# Application.net
KiCad netlist of a schematic drawn in EAGLE
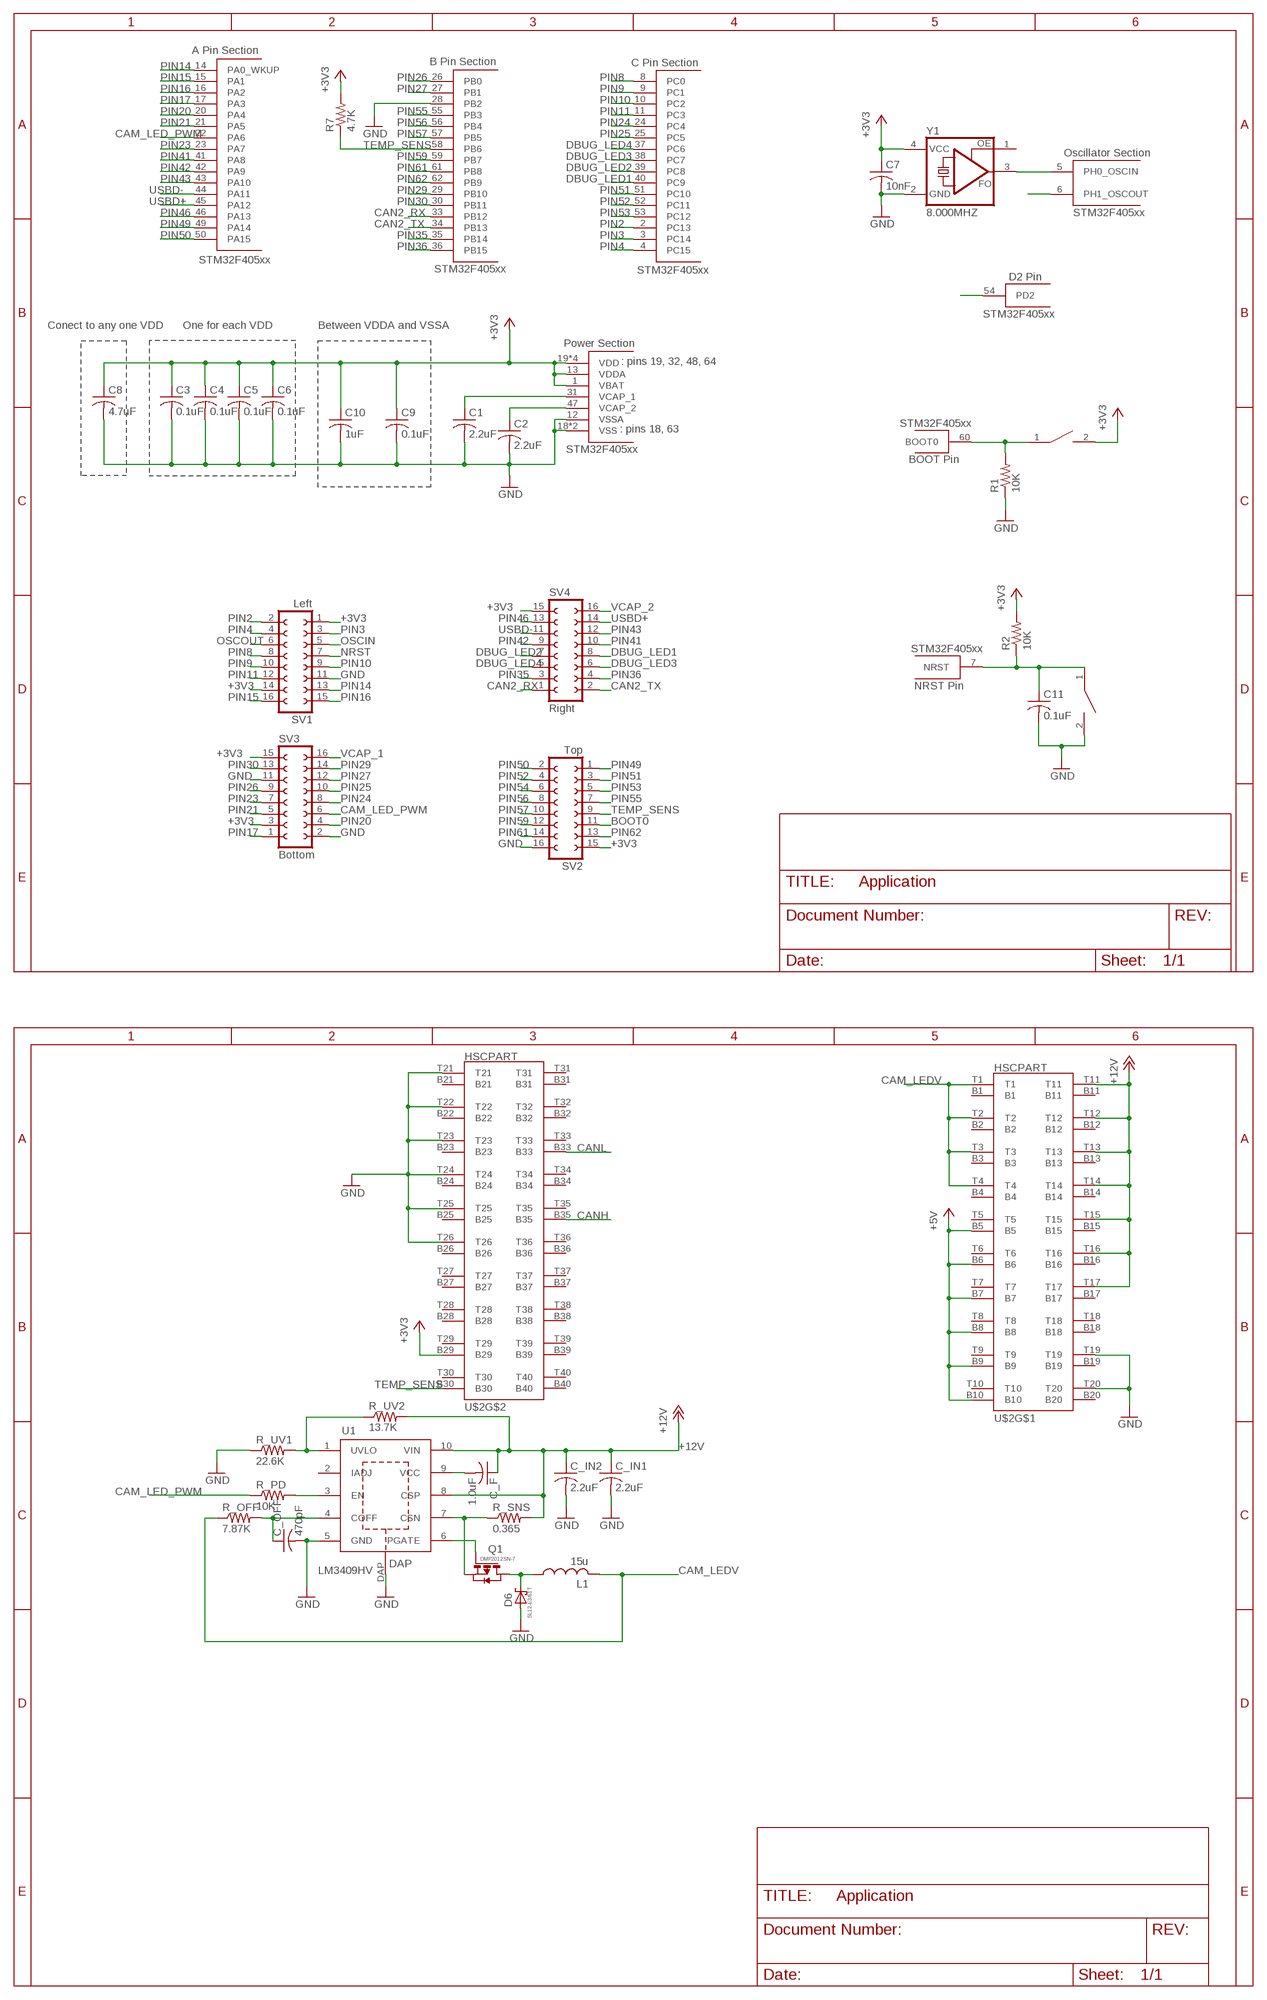
[diagram p0: schematic, sheet 1, part 1 of 2]
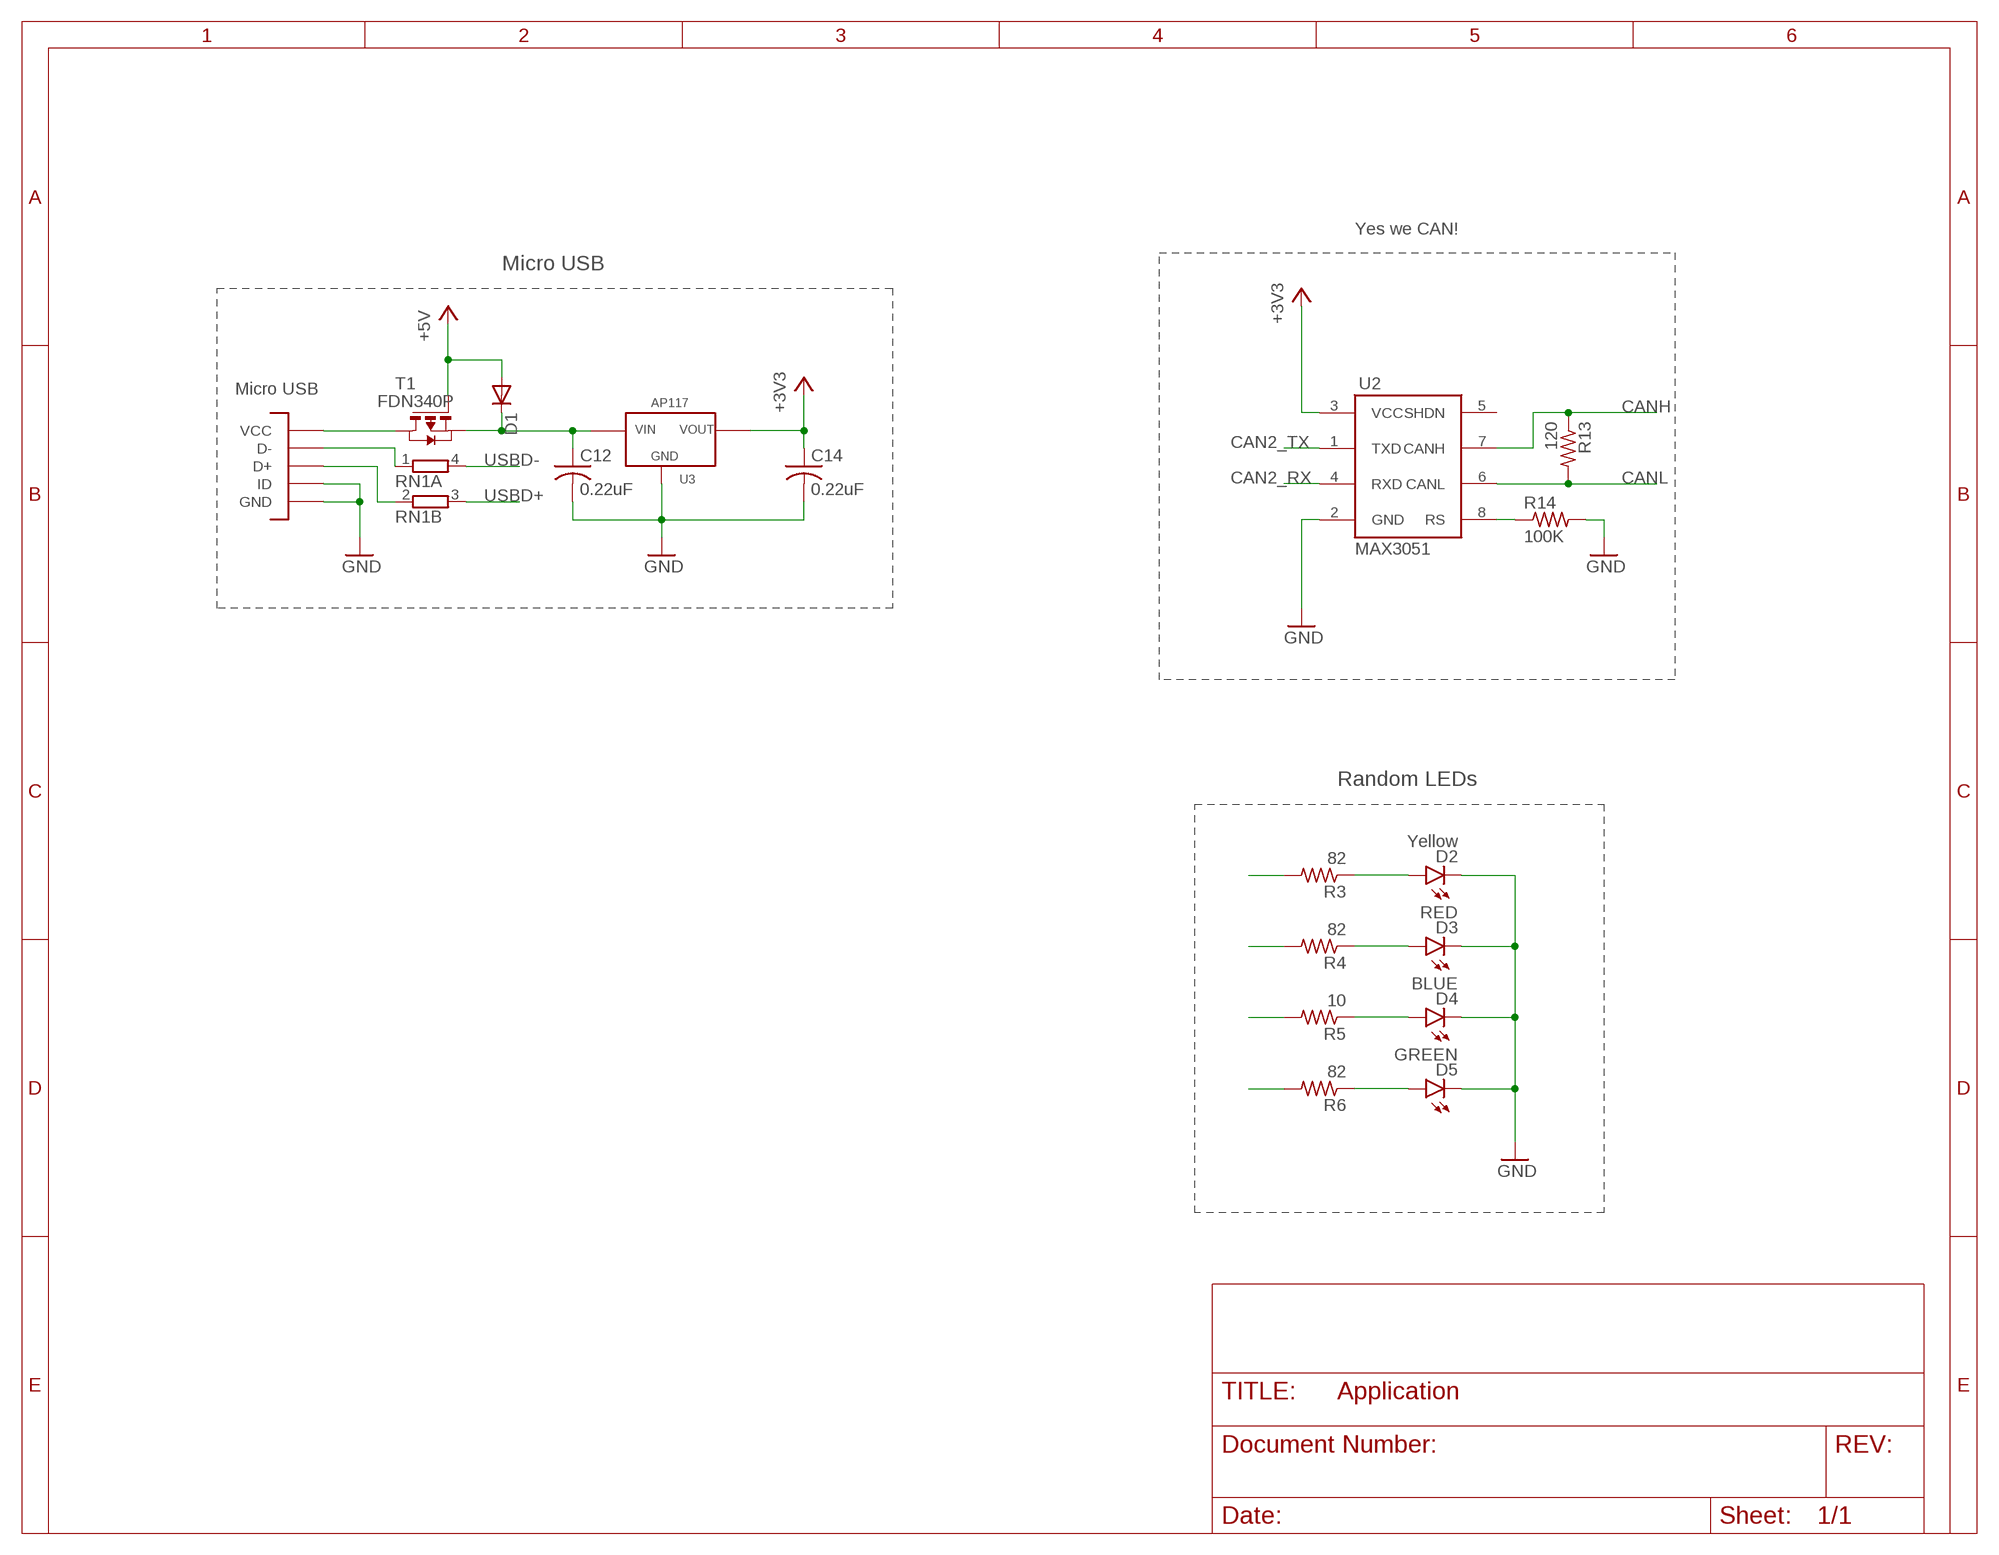
[diagram p1: schematic, sheet 1, part 2 of 2]

(export (version "E")
  (design (tool "Eeschema 10.0.6"))
  (components
    (comp (ref "C1")
      (value "2.2uF")
      (footprint "eagle-import:C0603")
      (libsource (lib "eagle-import") (part "C-USC0603"))
    )
    (comp (ref "C2")
      (value "2.2uF")
      (footprint "eagle-import:C0603")
      (libsource (lib "eagle-import") (part "C-USC0603"))
    )
    (comp (ref "C3")
      (value "0.1uF")
      (footprint "eagle-import:C0603")
      (libsource (lib "eagle-import") (part "C-USC0603"))
    )
    (comp (ref "C4")
      (value "0.1uF")
      (footprint "eagle-import:C0603")
      (libsource (lib "eagle-import") (part "C-USC0603"))
    )
    (comp (ref "C5")
      (value "0.1uF")
      (footprint "eagle-import:C0603")
      (libsource (lib "eagle-import") (part "C-USC0603"))
    )
    (comp (ref "C6")
      (value "0.1uF")
      (footprint "eagle-import:C0603")
      (libsource (lib "eagle-import") (part "C-USC0603"))
    )
    (comp (ref "C7")
      (value "10nF")
      (footprint "eagle-import:C0603")
      (libsource (lib "eagle-import") (part "C-USC0603"))
    )
    (comp (ref "C8")
      (value "4.7uF")
      (footprint "eagle-import:C0603")
      (libsource (lib "eagle-import") (part "C-USC0603"))
    )
    (comp (ref "C9")
      (value "0.1uF")
      (footprint "eagle-import:C0603")
      (libsource (lib "eagle-import") (part "C-USC0603"))
    )
    (comp (ref "C10")
      (value "1uF")
      (footprint "eagle-import:C0603")
      (libsource (lib "eagle-import") (part "C-USC0603"))
    )
    (comp (ref "C11")
      (value "0.1uF")
      (footprint "eagle-import:C0603")
      (libsource (lib "eagle-import") (part "C-USC0603"))
    )
    (comp (ref "C12")
      (value "0.22uF")
      (footprint "eagle-import:C0603")
      (libsource (lib "eagle-import") (part "C-USC0603"))
    )
    (comp (ref "C14")
      (value "0.22uF")
      (footprint "eagle-import:C0603")
      (libsource (lib "eagle-import") (part "C-USC0603"))
    )
    (comp (ref "C_F")
      (value "1.0uF")
      (footprint "eagle-import:C0603")
      (libsource (lib "eagle-import") (part "resistor_C-USC0603"))
    )
    (comp (ref "C_IN1")
      (value "2.2uF")
      (footprint "eagle-import:C0603")
      (libsource (lib "eagle-import") (part "resistor_C-USC0603"))
    )
    (comp (ref "C_IN2")
      (value "2.2uF")
      (footprint "eagle-import:C0603")
      (libsource (lib "eagle-import") (part "resistor_C-USC0603"))
    )
    (comp (ref "C_OFF")
      (value "470pF")
      (footprint "eagle-import:C0603")
      (libsource (lib "eagle-import") (part "resistor_C-USC0603"))
    )
    (comp (ref "D1")
      (value "DIODE-DO-214AC")
      (footprint "eagle-import:DO-214AC")
      (libsource (lib "eagle-import") (part "DIODE-DO-214AC"))
    )
    (comp (ref "D2")
      (value "Yellow")
      (footprint "eagle-import:LED-0603")
      (libsource (lib "eagle-import") (part "LED-YELLOW0603"))
    )
    (comp (ref "D3")
      (value "RED")
      (footprint "eagle-import:LED-0603")
      (libsource (lib "eagle-import") (part "LED-RED0603"))
    )
    (comp (ref "D4")
      (value "BLUE")
      (footprint "eagle-import:LED-0603")
      (libsource (lib "eagle-import") (part "LED-BLUE0603"))
    )
    (comp (ref "D5")
      (value "GREEN")
      (footprint "eagle-import:LED-0603")
      (libsource (lib "eagle-import") (part "LED-GREEN0603"))
    )
    (comp (ref "D6")
      (value "SL12-E3/61T")
      (footprint "eagle-import:SL12-E3_61T")
      (libsource (lib "eagle-import") (part "SL12-E3/61T"))
    )
    (comp (ref "L1")
      (value "15u")
      (footprint "eagle-import:SRN8040")
      (libsource (lib "eagle-import") (part "SRN8040"))
    )
    (comp (ref "Q1")
      (value "DMP2012SN-7")
      (footprint "eagle-import:DMP2012SN-7")
      (libsource (lib "eagle-import") (part "DMP2012SN-7"))
    )
    (comp (ref "R1")
      (value "10K")
      (footprint "eagle-import:R0603")
      (libsource (lib "eagle-import") (part "rcl_R-US_R0603"))
    )
    (comp (ref "R2")
      (value "10K")
      (footprint "eagle-import:R0603")
      (libsource (lib "eagle-import") (part "rcl_R-US_R0603"))
    )
    (comp (ref "R3")
      (value "82")
      (footprint "eagle-import:R0603")
      (libsource (lib "eagle-import") (part "rcl_R-US_R0603"))
    )
    (comp (ref "R4")
      (value "82")
      (footprint "eagle-import:R0603")
      (libsource (lib "eagle-import") (part "rcl_R-US_R0603"))
    )
    (comp (ref "R5")
      (value "10")
      (footprint "eagle-import:R0603")
      (libsource (lib "eagle-import") (part "rcl_R-US_R0603"))
    )
    (comp (ref "R6")
      (value "82")
      (footprint "eagle-import:R0603")
      (libsource (lib "eagle-import") (part "rcl_R-US_R0603"))
    )
    (comp (ref "R7")
      (value "4.7K")
      (footprint "eagle-import:R0603")
      (libsource (lib "eagle-import") (part "rcl_R-US_R0603"))
    )
    (comp (ref "R13")
      (value "120")
      (footprint "eagle-import:R0603")
      (libsource (lib "eagle-import") (part "rcl_R-US_R0603"))
    )
    (comp (ref "R14")
      (value "100K")
      (footprint "eagle-import:R0603")
      (libsource (lib "eagle-import") (part "rcl_R-US_R0603"))
    )
    (comp (ref "RN1")
      (value "2R-NEXBV4V")
      (footprint "eagle-import:EXBV4V")
      (fields (field (name "MF") "Rohm Semiconductor") (field (name "MPN") "MNR12ERAPJ220"))
      (libsource (lib "eagle-import") (part "2R-NEXBV4V"))
    )
    (comp (ref "R_OFF")
      (value "7.87K")
      (footprint "eagle-import:R0603")
      (libsource (lib "eagle-import") (part "R-US_R0603"))
    )
    (comp (ref "R_PD")
      (value "10K")
      (footprint "eagle-import:R0603")
      (libsource (lib "eagle-import") (part "R-US_R0603"))
    )
    (comp (ref "R_SNS")
      (value "0.365")
      (footprint "eagle-import:R2512")
      (libsource (lib "eagle-import") (part "R-US_R2512"))
    )
    (comp (ref "R_UV1")
      (value "22.6K")
      (footprint "eagle-import:R0603")
      (libsource (lib "eagle-import") (part "R-US_R0603"))
    )
    (comp (ref "R_UV2")
      (value "13.7K")
      (footprint "eagle-import:R0603")
      (libsource (lib "eagle-import") (part "R-US_R0603"))
    )
    (comp (ref "S1")
      (value "BOOT")
      (footprint "eagle-import:SW_2512")
      (libsource (lib "eagle-import") (part "SWITCH"))
    )
    (comp (ref "S2")
      (value "RESET")
      (footprint "eagle-import:SW_2512")
      (libsource (lib "eagle-import") (part "SWITCH"))
    )
    (comp (ref "SV1")
      (value "Left")
      (footprint "eagle-import:FE08-2")
      (libsource (lib "eagle-import") (part "FE08-2"))
    )
    (comp (ref "SV2")
      (value "Top")
      (footprint "eagle-import:FE08-2")
      (libsource (lib "eagle-import") (part "FE08-2"))
    )
    (comp (ref "SV3")
      (value "Bottom")
      (footprint "eagle-import:FE08-2")
      (libsource (lib "eagle-import") (part "FE08-2"))
    )
    (comp (ref "SV4")
      (value "Right")
      (footprint "eagle-import:FE08-2")
      (libsource (lib "eagle-import") (part "FE08-2"))
    )
    (comp (ref "T1")
      (value "FDN340P")
      (footprint "eagle-import:SOT-23")
      (libsource (lib "eagle-import") (part "FDN340P"))
    )
    (comp (ref "U$1")
      (value "STM32F405")
      (footprint "eagle-import:LQFP64")
      (libsource (lib "eagle-import") (part "STM32F405"))
    )
    (comp (ref "U$2")
      (value "HSCPART")
      (footprint "eagle-import:HSC8-40PINOUUT")
      (libsource (lib "eagle-import") (part "HSCPART"))
    )
    (comp (ref "U$4")
      (value "MICROUSB")
      (footprint "eagle-import:MICRO_B")
      (libsource (lib "eagle-import") (part "MICROUSB"))
    )
    (comp (ref "U1")
      (value "LM3409HV")
      (footprint "eagle-import:VSSOP-10")
      (libsource (lib "eagle-import") (part "LM3409HV'LM3409HV'"))
    )
    (comp (ref "U2")
      (value "MAX3051")
      (footprint "eagle-import:SOT23-8L")
      (libsource (lib "eagle-import") (part "MAX3051MAX3051"))
    )
    (comp (ref "U3")
      (value "U3")
      (footprint "eagle-import:SOT223")
      (libsource (lib "eagle-import") (part "AP1117_LIN_REG"))
    )
    (comp (ref "Y1")
      (value "8.000MHZ")
      (footprint "eagle-import:ASF")
      (libsource (lib "eagle-import") (part "ASF"))
    )
  )
  (nets
    (net (code "1") (name "+3V3") (class "Default")
      (node (ref "C10") (pin "1") (pinfunction "1_1") (pintype "passive"))
      (node (ref "C14") (pin "1") (pinfunction "1_1") (pintype "passive"))
      (node (ref "C3") (pin "1") (pinfunction "1_1") (pintype "passive"))
      (node (ref "C4") (pin "1") (pinfunction "1_1") (pintype "passive"))
      (node (ref "C5") (pin "1") (pinfunction "1_1") (pintype "passive"))
      (node (ref "C6") (pin "1") (pinfunction "1_1") (pintype "passive"))
      (node (ref "C7") (pin "1") (pinfunction "1_1") (pintype "passive"))
      (node (ref "C8") (pin "1") (pinfunction "1_1") (pintype "passive"))
      (node (ref "C9") (pin "1") (pinfunction "1_1") (pintype "passive"))
      (node (ref "R2") (pin "2") (pinfunction "2_2") (pintype "passive"))
      (node (ref "R7") (pin "2") (pinfunction "2_2") (pintype "passive"))
      (node (ref "S1") (pin "2") (pinfunction "P$2_2") (pintype "bidirectional"))
      (node (ref "SV1") (pin "1") (pinfunction "1_1") (pintype "passive"))
      (node (ref "SV1") (pin "14") (pinfunction "14_14") (pintype "passive"))
      (node (ref "SV2") (pin "15") (pinfunction "15_15") (pintype "passive"))
      (node (ref "SV3") (pin "15") (pinfunction "15_15") (pintype "passive"))
      (node (ref "SV3") (pin "3") (pinfunction "3_3") (pintype "passive"))
      (node (ref "SV4") (pin "15") (pinfunction "15_15") (pintype "passive"))
      (node (ref "U$1") (pin "1") (pinfunction "VBAT_1") (pintype "bidirectional"))
      (node (ref "U$1") (pin "13") (pinfunction "VDDA_13") (pintype "bidirectional"))
      (node (ref "U$1") (pin "19") (pinfunction "VDD_19") (pintype "bidirectional"))
      (node (ref "U$1") (pin "32") (pinfunction "VDD_32") (pintype "bidirectional"))
      (node (ref "U$1") (pin "48") (pinfunction "VDD_48") (pintype "bidirectional"))
      (node (ref "U$1") (pin "64") (pinfunction "VDD_64") (pintype "bidirectional"))
      (node (ref "U$2") (pin "B29") (pinfunction "B29_B29") (pintype "bidirectional"))
      (node (ref "U2") (pin "3") (pinfunction "VCC_3") (pintype "bidirectional"))
      (node (ref "U3") (pin "TAB") (pinfunction "VOUT_TAB") (pintype "output"))
      (node (ref "U3") (pin "VOUT") (pinfunction "VOUT_VOUT") (pintype "output"))
      (node (ref "Y1") (pin "4") (pinfunction "VCC_4") (pintype "power_in"))
    )
    (net (code "2") (name "+5V") (class "Default")
      (node (ref "D1") (pin "A") (pinfunction "A_A") (pintype "passive"))
      (node (ref "T1") (pin "3") (pinfunction "G_3") (pintype "passive"))
      (node (ref "U$2") (pin "B10") (pinfunction "B10_B10") (pintype "bidirectional"))
      (node (ref "U$2") (pin "B5") (pinfunction "B5_B5") (pintype "bidirectional"))
      (node (ref "U$2") (pin "B6") (pinfunction "B6_B6") (pintype "bidirectional"))
      (node (ref "U$2") (pin "B7") (pinfunction "B7_B7") (pintype "bidirectional"))
      (node (ref "U$2") (pin "B8") (pinfunction "B8_B8") (pintype "bidirectional"))
      (node (ref "U$2") (pin "B9") (pinfunction "B9_B9") (pintype "bidirectional"))
    )
    (net (code "3") (name "+12V") (class "Default")
      (node (ref "C_F") (pin "1") (pinfunction "1_1") (pintype "passive"))
      (node (ref "C_IN1") (pin "1") (pinfunction "1_1") (pintype "passive"))
      (node (ref "C_IN2") (pin "1") (pinfunction "1_1") (pintype "passive"))
      (node (ref "R_SNS") (pin "2") (pinfunction "2_2") (pintype "passive"))
      (node (ref "R_UV2") (pin "2") (pinfunction "2_2") (pintype "passive"))
      (node (ref "U$2") (pin "T11") (pinfunction "T11_T11") (pintype "bidirectional"))
      (node (ref "U$2") (pin "T12") (pinfunction "T12_T12") (pintype "bidirectional"))
      (node (ref "U$2") (pin "T13") (pinfunction "T13_T13") (pintype "bidirectional"))
      (node (ref "U$2") (pin "T14") (pinfunction "T14_T14") (pintype "bidirectional"))
      (node (ref "U$2") (pin "T15") (pinfunction "T15_T15") (pintype "bidirectional"))
      (node (ref "U$2") (pin "T16") (pinfunction "T16_T16") (pintype "bidirectional"))
      (node (ref "U$2") (pin "T17") (pinfunction "T17_T17") (pintype "bidirectional"))
      (node (ref "U1") (pin "10") (pinfunction "VIN_10") (pintype "bidirectional"))
      (node (ref "U1") (pin "8") (pinfunction "CSP_8") (pintype "bidirectional"))
    )
    (net (code "4") (name "/BOOT0") (class "Default")
      (node (ref "R1") (pin "2") (pinfunction "2_2") (pintype "passive"))
      (node (ref "S1") (pin "1") (pinfunction "P$1_1") (pintype "bidirectional"))
      (node (ref "SV2") (pin "11") (pinfunction "11_11") (pintype "passive"))
      (node (ref "U$1") (pin "60") (pinfunction "BOOT0_60") (pintype "bidirectional"))
    )
    (net (code "5") (name "/CAM_LEDV") (class "Default")
      (node (ref "L1") (pin "2") (pinfunction "2_2") (pintype "passive"))
      (node (ref "R_OFF") (pin "1") (pinfunction "1_1") (pintype "passive"))
      (node (ref "U$2") (pin "T1") (pinfunction "T1_T1") (pintype "bidirectional"))
      (node (ref "U$2") (pin "T2") (pinfunction "T2_T2") (pintype "bidirectional"))
      (node (ref "U$2") (pin "T3") (pinfunction "T3_T3") (pintype "bidirectional"))
      (node (ref "U$2") (pin "T4") (pinfunction "T4_T4") (pintype "bidirectional"))
    )
    (net (code "6") (name "/CAM_LED_PWM") (class "Default")
      (node (ref "R_PD") (pin "1") (pinfunction "1_1") (pintype "passive"))
      (node (ref "SV3") (pin "6") (pinfunction "6_6") (pintype "passive"))
      (node (ref "U$1") (pin "22") (pinfunction "PA6_22") (pintype "bidirectional"))
    )
    (net (code "7") (name "/CAN2_RX") (class "Default")
      (node (ref "SV4") (pin "1") (pinfunction "1_1") (pintype "passive"))
      (node (ref "U$1") (pin "33") (pinfunction "PB12_33") (pintype "bidirectional"))
      (node (ref "U2") (pin "4") (pinfunction "RXD_4") (pintype "bidirectional"))
    )
    (net (code "8") (name "/CAN2_TX") (class "Default")
      (node (ref "SV4") (pin "2") (pinfunction "2_2") (pintype "passive"))
      (node (ref "U$1") (pin "34") (pinfunction "PB13_34") (pintype "bidirectional"))
      (node (ref "U2") (pin "1") (pinfunction "TXD_1") (pintype "bidirectional"))
    )
    (net (code "9") (name "/CANH") (class "Default")
      (node (ref "R13") (pin "1") (pinfunction "1_1") (pintype "passive"))
      (node (ref "U$2") (pin "B35") (pinfunction "B35_B35") (pintype "bidirectional"))
      (node (ref "U2") (pin "7") (pinfunction "CANH_7") (pintype "bidirectional"))
    )
    (net (code "10") (name "/CANL") (class "Default")
      (node (ref "R13") (pin "2") (pinfunction "2_2") (pintype "passive"))
      (node (ref "U$2") (pin "B33") (pinfunction "B33_B33") (pintype "bidirectional"))
      (node (ref "U2") (pin "6") (pinfunction "CANL_6") (pintype "bidirectional"))
    )
    (net (code "11") (name "/DBUG_LED1") (class "Default")
      (node (ref "R3") (pin "2") (pinfunction "2_2") (pintype "passive"))
      (node (ref "SV4") (pin "8") (pinfunction "8_8") (pintype "passive"))
      (node (ref "U$1") (pin "40") (pinfunction "PC9_40") (pintype "bidirectional"))
    )
    (net (code "12") (name "/DBUG_LED2") (class "Default")
      (node (ref "R4") (pin "2") (pinfunction "2_2") (pintype "passive"))
      (node (ref "SV4") (pin "7") (pinfunction "7_7") (pintype "passive"))
      (node (ref "U$1") (pin "39") (pinfunction "PC8_39") (pintype "bidirectional"))
    )
    (net (code "13") (name "/DBUG_LED3") (class "Default")
      (node (ref "R5") (pin "2") (pinfunction "2_2") (pintype "passive"))
      (node (ref "SV4") (pin "6") (pinfunction "6_6") (pintype "passive"))
      (node (ref "U$1") (pin "38") (pinfunction "PC7_38") (pintype "bidirectional"))
    )
    (net (code "14") (name "/DBUG_LED4") (class "Default")
      (node (ref "R6") (pin "2") (pinfunction "2_2") (pintype "passive"))
      (node (ref "SV4") (pin "5") (pinfunction "5_5") (pintype "passive"))
      (node (ref "U$1") (pin "37") (pinfunction "PC6_37") (pintype "bidirectional"))
    )
    (net (code "15") (name "/NRST") (class "Default")
      (node (ref "C11") (pin "1") (pinfunction "1_1") (pintype "passive"))
      (node (ref "R2") (pin "1") (pinfunction "1_1") (pintype "passive"))
      (node (ref "S2") (pin "1") (pinfunction "P$1_1") (pintype "bidirectional"))
      (node (ref "SV1") (pin "7") (pinfunction "7_7") (pintype "passive"))
      (node (ref "U$1") (pin "7") (pinfunction "NRST_7") (pintype "bidirectional"))
    )
    (net (code "16") (name "/OSCIN") (class "Default")
      (node (ref "SV1") (pin "5") (pinfunction "5_5") (pintype "passive"))
      (node (ref "U$1") (pin "5") (pinfunction "PH0_OSCIN_5") (pintype "bidirectional"))
      (node (ref "Y1") (pin "3") (pinfunction "FO_3") (pintype "output"))
    )
    (net (code "17") (name "/OSCOUT") (class "Default")
      (node (ref "SV1") (pin "6") (pinfunction "6_6") (pintype "passive"))
      (node (ref "U$1") (pin "6") (pinfunction "PH1_OSCOUT_6") (pintype "bidirectional"))
    )
    (net (code "18") (name "/PIN2") (class "Default")
      (node (ref "SV1") (pin "2") (pinfunction "2_2") (pintype "passive"))
      (node (ref "U$1") (pin "2") (pinfunction "PC13_2") (pintype "bidirectional"))
    )
    (net (code "19") (name "/PIN3") (class "Default")
      (node (ref "SV1") (pin "3") (pinfunction "3_3") (pintype "passive"))
      (node (ref "U$1") (pin "3") (pinfunction "PC14_3") (pintype "bidirectional"))
    )
    (net (code "20") (name "/PIN4") (class "Default")
      (node (ref "SV1") (pin "4") (pinfunction "4_4") (pintype "passive"))
      (node (ref "U$1") (pin "4") (pinfunction "PC15_4") (pintype "bidirectional"))
    )
    (net (code "21") (name "/PIN8") (class "Default")
      (node (ref "SV1") (pin "8") (pinfunction "8_8") (pintype "passive"))
      (node (ref "U$1") (pin "8") (pinfunction "PC0_8") (pintype "bidirectional"))
    )
    (net (code "22") (name "/PIN9") (class "Default")
      (node (ref "SV1") (pin "10") (pinfunction "10_10") (pintype "passive"))
      (node (ref "U$1") (pin "9") (pinfunction "PC1_9") (pintype "bidirectional"))
    )
    (net (code "23") (name "/PIN10") (class "Default")
      (node (ref "SV1") (pin "9") (pinfunction "9_9") (pintype "passive"))
      (node (ref "U$1") (pin "10") (pinfunction "PC2_10") (pintype "bidirectional"))
    )
    (net (code "24") (name "/PIN11") (class "Default")
      (node (ref "SV1") (pin "12") (pinfunction "12_12") (pintype "passive"))
      (node (ref "U$1") (pin "11") (pinfunction "PC3_11") (pintype "bidirectional"))
    )
    (net (code "25") (name "/PIN14") (class "Default")
      (node (ref "SV1") (pin "13") (pinfunction "13_13") (pintype "passive"))
      (node (ref "U$1") (pin "14") (pinfunction "PA0_WKUP_14") (pintype "bidirectional"))
    )
    (net (code "26") (name "/PIN15") (class "Default")
      (node (ref "SV1") (pin "16") (pinfunction "16_16") (pintype "passive"))
      (node (ref "U$1") (pin "15") (pinfunction "PA1_15") (pintype "bidirectional"))
    )
    (net (code "27") (name "/PIN16") (class "Default")
      (node (ref "SV1") (pin "15") (pinfunction "15_15") (pintype "passive"))
      (node (ref "U$1") (pin "16") (pinfunction "PA2_16") (pintype "bidirectional"))
    )
    (net (code "28") (name "/PIN17") (class "Default")
      (node (ref "SV3") (pin "1") (pinfunction "1_1") (pintype "passive"))
      (node (ref "U$1") (pin "17") (pinfunction "PA3_17") (pintype "bidirectional"))
    )
    (net (code "29") (name "/PIN20") (class "Default")
      (node (ref "SV3") (pin "4") (pinfunction "4_4") (pintype "passive"))
      (node (ref "U$1") (pin "20") (pinfunction "PA4_20") (pintype "bidirectional"))
    )
    (net (code "30") (name "/PIN21") (class "Default")
      (node (ref "SV3") (pin "5") (pinfunction "5_5") (pintype "passive"))
      (node (ref "U$1") (pin "21") (pinfunction "PA5_21") (pintype "bidirectional"))
    )
    (net (code "31") (name "/PIN23") (class "Default")
      (node (ref "SV3") (pin "7") (pinfunction "7_7") (pintype "passive"))
      (node (ref "U$1") (pin "23") (pinfunction "PA7_23") (pintype "bidirectional"))
    )
    (net (code "32") (name "/PIN24") (class "Default")
      (node (ref "SV3") (pin "8") (pinfunction "8_8") (pintype "passive"))
      (node (ref "U$1") (pin "24") (pinfunction "PC4_24") (pintype "bidirectional"))
    )
    (net (code "33") (name "/PIN25") (class "Default")
      (node (ref "SV3") (pin "10") (pinfunction "10_10") (pintype "passive"))
      (node (ref "U$1") (pin "25") (pinfunction "PC5_25") (pintype "bidirectional"))
    )
    (net (code "34") (name "/PIN26") (class "Default")
      (node (ref "SV3") (pin "9") (pinfunction "9_9") (pintype "passive"))
      (node (ref "U$1") (pin "26") (pinfunction "PB0_26") (pintype "bidirectional"))
    )
    (net (code "35") (name "/PIN27") (class "Default")
      (node (ref "SV3") (pin "12") (pinfunction "12_12") (pintype "passive"))
      (node (ref "U$1") (pin "27") (pinfunction "PB1_27") (pintype "bidirectional"))
    )
    (net (code "36") (name "/PIN29") (class "Default")
      (node (ref "SV3") (pin "14") (pinfunction "14_14") (pintype "passive"))
      (node (ref "U$1") (pin "29") (pinfunction "PB10_29") (pintype "bidirectional"))
    )
    (net (code "37") (name "/PIN30") (class "Default")
      (node (ref "SV3") (pin "13") (pinfunction "13_13") (pintype "passive"))
      (node (ref "U$1") (pin "30") (pinfunction "PB11_30") (pintype "bidirectional"))
    )
    (net (code "38") (name "/PIN35") (class "Default")
      (node (ref "SV4") (pin "3") (pinfunction "3_3") (pintype "passive"))
      (node (ref "U$1") (pin "35") (pinfunction "PB14_35") (pintype "bidirectional"))
    )
    (net (code "39") (name "/PIN36") (class "Default")
      (node (ref "SV4") (pin "4") (pinfunction "4_4") (pintype "passive"))
      (node (ref "U$1") (pin "36") (pinfunction "PB15_36") (pintype "bidirectional"))
    )
    (net (code "40") (name "/PIN41") (class "Default")
      (node (ref "SV4") (pin "10") (pinfunction "10_10") (pintype "passive"))
      (node (ref "U$1") (pin "41") (pinfunction "PA8_41") (pintype "bidirectional"))
    )
    (net (code "41") (name "/PIN42") (class "Default")
      (node (ref "SV4") (pin "9") (pinfunction "9_9") (pintype "passive"))
      (node (ref "U$1") (pin "42") (pinfunction "PA9_42") (pintype "bidirectional"))
    )
    (net (code "42") (name "/PIN43") (class "Default")
      (node (ref "SV4") (pin "12") (pinfunction "12_12") (pintype "passive"))
      (node (ref "U$1") (pin "43") (pinfunction "PA10_43") (pintype "bidirectional"))
    )
    (net (code "43") (name "/PIN46") (class "Default")
      (node (ref "SV4") (pin "13") (pinfunction "13_13") (pintype "passive"))
      (node (ref "U$1") (pin "46") (pinfunction "PA13_46") (pintype "bidirectional"))
    )
    (net (code "44") (name "/PIN49") (class "Default")
      (node (ref "SV2") (pin "1") (pinfunction "1_1") (pintype "passive"))
      (node (ref "U$1") (pin "49") (pinfunction "PA14_49") (pintype "bidirectional"))
    )
    (net (code "45") (name "/PIN50") (class "Default")
      (node (ref "SV2") (pin "2") (pinfunction "2_2") (pintype "passive"))
      (node (ref "U$1") (pin "50") (pinfunction "PA15_50") (pintype "bidirectional"))
    )
    (net (code "46") (name "/PIN51") (class "Default")
      (node (ref "SV2") (pin "3") (pinfunction "3_3") (pintype "passive"))
      (node (ref "U$1") (pin "51") (pinfunction "PC10_51") (pintype "bidirectional"))
    )
    (net (code "47") (name "/PIN52") (class "Default")
      (node (ref "SV2") (pin "4") (pinfunction "4_4") (pintype "passive"))
      (node (ref "U$1") (pin "52") (pinfunction "PC11_52") (pintype "bidirectional"))
    )
    (net (code "48") (name "/PIN53") (class "Default")
      (node (ref "SV2") (pin "5") (pinfunction "5_5") (pintype "passive"))
      (node (ref "U$1") (pin "53") (pinfunction "PC12_53") (pintype "bidirectional"))
    )
    (net (code "49") (name "/PIN54") (class "Default")
      (node (ref "SV2") (pin "6") (pinfunction "6_6") (pintype "passive"))
      (node (ref "U$1") (pin "54") (pinfunction "PD2_54") (pintype "bidirectional"))
    )
    (net (code "50") (name "/PIN55") (class "Default")
      (node (ref "SV2") (pin "7") (pinfunction "7_7") (pintype "passive"))
      (node (ref "U$1") (pin "55") (pinfunction "PB3_55") (pintype "bidirectional"))
    )
    (net (code "51") (name "/PIN56") (class "Default")
      (node (ref "SV2") (pin "8") (pinfunction "8_8") (pintype "passive"))
      (node (ref "U$1") (pin "56") (pinfunction "PB4_56") (pintype "bidirectional"))
    )
    (net (code "52") (name "/PIN57") (class "Default")
      (node (ref "SV2") (pin "10") (pinfunction "10_10") (pintype "passive"))
      (node (ref "U$1") (pin "57") (pinfunction "PB5_57") (pintype "bidirectional"))
    )
    (net (code "53") (name "/PIN59") (class "Default")
      (node (ref "SV2") (pin "12") (pinfunction "12_12") (pintype "passive"))
      (node (ref "U$1") (pin "59") (pinfunction "PB7_59") (pintype "bidirectional"))
    )
    (net (code "54") (name "/PIN61") (class "Default")
      (node (ref "SV2") (pin "14") (pinfunction "14_14") (pintype "passive"))
      (node (ref "U$1") (pin "61") (pinfunction "PB8_61") (pintype "bidirectional"))
    )
    (net (code "55") (name "/PIN62") (class "Default")
      (node (ref "SV2") (pin "13") (pinfunction "13_13") (pintype "passive"))
      (node (ref "U$1") (pin "62") (pinfunction "PB9_62") (pintype "bidirectional"))
    )
    (net (code "56") (name "/TEMP_SENS") (class "Default")
      (node (ref "R7") (pin "1") (pinfunction "1_1") (pintype "passive"))
      (node (ref "SV2") (pin "9") (pinfunction "9_9") (pintype "passive"))
      (node (ref "U$1") (pin "58") (pinfunction "PB6_58") (pintype "bidirectional"))
      (node (ref "U$2") (pin "B30") (pinfunction "B30_B30") (pintype "bidirectional"))
    )
    (net (code "57") (name "/USBD+") (class "Default")
      (node (ref "RN1") (pin "3") (pinfunction "2_3") (pintype "passive"))
      (node (ref "SV4") (pin "14") (pinfunction "14_14") (pintype "passive"))
      (node (ref "U$1") (pin "45") (pinfunction "PA12_45") (pintype "bidirectional"))
    )
    (net (code "58") (name "/USBD-") (class "Default")
      (node (ref "RN1") (pin "4") (pinfunction "2_4") (pintype "passive"))
      (node (ref "SV4") (pin "11") (pinfunction "11_11") (pintype "passive"))
      (node (ref "U$1") (pin "44") (pinfunction "PA11_44") (pintype "bidirectional"))
    )
    (net (code "59") (name "/VCAP_1") (class "Default")
      (node (ref "C1") (pin "1") (pinfunction "1_1") (pintype "passive"))
      (node (ref "SV3") (pin "16") (pinfunction "16_16") (pintype "passive"))
      (node (ref "U$1") (pin "31") (pinfunction "VCAP_1_31") (pintype "bidirectional"))
    )
    (net (code "60") (name "/VCAP_2") (class "Default")
      (node (ref "C2") (pin "1") (pinfunction "1_1") (pintype "passive"))
      (node (ref "SV4") (pin "16") (pinfunction "16_16") (pintype "passive"))
      (node (ref "U$1") (pin "47") (pinfunction "VCAP_2_47") (pintype "bidirectional"))
    )
    (net (code "61") (name "GND") (class "Default")
      (node (ref "C1") (pin "2") (pinfunction "2_2") (pintype "passive"))
      (node (ref "C10") (pin "2") (pinfunction "2_2") (pintype "passive"))
      (node (ref "C11") (pin "2") (pinfunction "2_2") (pintype "passive"))
      (node (ref "C12") (pin "2") (pinfunction "2_2") (pintype "passive"))
      (node (ref "C14") (pin "2") (pinfunction "2_2") (pintype "passive"))
      (node (ref "C2") (pin "2") (pinfunction "2_2") (pintype "passive"))
      (node (ref "C3") (pin "2") (pinfunction "2_2") (pintype "passive"))
      (node (ref "C4") (pin "2") (pinfunction "2_2") (pintype "passive"))
      (node (ref "C5") (pin "2") (pinfunction "2_2") (pintype "passive"))
      (node (ref "C6") (pin "2") (pinfunction "2_2") (pintype "passive"))
      (node (ref "C7") (pin "2") (pinfunction "2_2") (pintype "passive"))
      (node (ref "C8") (pin "2") (pinfunction "2_2") (pintype "passive"))
      (node (ref "C9") (pin "2") (pinfunction "2_2") (pintype "passive"))
      (node (ref "C_IN1") (pin "2") (pinfunction "2_2") (pintype "passive"))
      (node (ref "C_IN2") (pin "2") (pinfunction "2_2") (pintype "passive"))
      (node (ref "C_OFF") (pin "2") (pinfunction "2_2") (pintype "passive"))
      (node (ref "D2") (pin "C") (pinfunction "C_C") (pintype "passive"))
      (node (ref "D3") (pin "C") (pinfunction "C_C") (pintype "passive"))
      (node (ref "D4") (pin "C") (pinfunction "C_C") (pintype "passive"))
      (node (ref "D5") (pin "C") (pinfunction "C_C") (pintype "passive"))
      (node (ref "D6") (pin "2") (pinfunction "A_2") (pintype "passive"))
      (node (ref "R1") (pin "1") (pinfunction "1_1") (pintype "passive"))
      (node (ref "R14") (pin "2") (pinfunction "2_2") (pintype "passive"))
      (node (ref "R_UV1") (pin "1") (pinfunction "1_1") (pintype "passive"))
      (node (ref "S2") (pin "2") (pinfunction "P$2_2") (pintype "bidirectional"))
      (node (ref "SV1") (pin "11") (pinfunction "11_11") (pintype "passive"))
      (node (ref "SV2") (pin "16") (pinfunction "16_16") (pintype "passive"))
      (node (ref "SV3") (pin "11") (pinfunction "11_11") (pintype "passive"))
      (node (ref "SV3") (pin "2") (pinfunction "2_2") (pintype "passive"))
      (node (ref "U$1") (pin "12") (pinfunction "VSSA_12") (pintype "bidirectional"))
      (node (ref "U$1") (pin "18") (pinfunction "VSS_18") (pintype "bidirectional"))
      (node (ref "U$1") (pin "28") (pinfunction "PB2_28") (pintype "bidirectional"))
      (node (ref "U$1") (pin "63") (pinfunction "VSS_63") (pintype "bidirectional"))
      (node (ref "U$2") (pin "T19") (pinfunction "T19_T19") (pintype "bidirectional"))
      (node (ref "U$2") (pin "T20") (pinfunction "T20_T20") (pintype "bidirectional"))
      (node (ref "U$2") (pin "T21") (pinfunction "T21_T21") (pintype "bidirectional"))
      (node (ref "U$2") (pin "T22") (pinfunction "T22_T22") (pintype "bidirectional"))
      (node (ref "U$2") (pin "T23") (pinfunction "T23_T23") (pintype "bidirectional"))
      (node (ref "U$2") (pin "T24") (pinfunction "T24_T24") (pintype "bidirectional"))
      (node (ref "U$2") (pin "T25") (pinfunction "T25_T25") (pintype "bidirectional"))
      (node (ref "U$2") (pin "T26") (pinfunction "T26_T26") (pintype "bidirectional"))
      (node (ref "U$4") (pin "GND1") (pinfunction "GND_GND1") (pintype "bidirectional"))
      (node (ref "U$4") (pin "GND2") (pinfunction "GND_GND2") (pintype "bidirectional"))
      (node (ref "U$4") (pin "GND3") (pinfunction "GND_GND3") (pintype "bidirectional"))
      (node (ref "U$4") (pin "GND4") (pinfunction "GND_GND4") (pintype "bidirectional"))
      (node (ref "U$4") (pin "GND7") (pinfunction "GND_GND7") (pintype "bidirectional"))
      (node (ref "U$4") (pin "GND8") (pinfunction "GND_GND8") (pintype "bidirectional"))
      (node (ref "U$4") (pin "P4") (pinfunction "ID_P4") (pintype "bidirectional"))
      (node (ref "U$4") (pin "P5") (pinfunction "GND_P5") (pintype "bidirectional"))
      (node (ref "U1") (pin "5") (pinfunction "GND_5") (pintype "bidirectional"))
      (node (ref "U1") (pin "DAP") (pinfunction "DAP_DAP") (pintype "bidirectional"))
      (node (ref "U2") (pin "2") (pinfunction "GND_2") (pintype "bidirectional"))
      (node (ref "U3") (pin "GND") (pinfunction "GND_GND") (pintype "bidirectional"))
      (node (ref "Y1") (pin "2") (pinfunction "GND_2") (pintype "power_in"))
    )
    (net (code "62") (name "Net-(D2-PadA)") (class "Default")
      (node (ref "D2") (pin "A") (pinfunction "A_A") (pintype "passive"))
      (node (ref "R3") (pin "1") (pinfunction "1_1") (pintype "passive"))
    )
    (net (code "63") (name "Net-(D3-PadA)") (class "Default")
      (node (ref "D3") (pin "A") (pinfunction "A_A") (pintype "passive"))
      (node (ref "R4") (pin "1") (pinfunction "1_1") (pintype "passive"))
    )
    (net (code "64") (name "Net-(D4-PadA)") (class "Default")
      (node (ref "D4") (pin "A") (pinfunction "A_A") (pintype "passive"))
      (node (ref "R5") (pin "1") (pinfunction "1_1") (pintype "passive"))
    )
    (net (code "65") (name "Net-(D5-PadA)") (class "Default")
      (node (ref "D5") (pin "A") (pinfunction "A_A") (pintype "passive"))
      (node (ref "R6") (pin "1") (pinfunction "1_1") (pintype "passive"))
    )
    (net (code "66") (name "Net-(D6-C)") (class "Default")
      (node (ref "D6") (pin "1") (pinfunction "C_1") (pintype "passive"))
      (node (ref "L1") (pin "1") (pinfunction "1_1") (pintype "passive"))
      (node (ref "Q1") (pin "1") (pinfunction "D_1") (pintype "passive"))
    )
    (net (code "67") (name "Net-(Q1-G)") (class "Default")
      (node (ref "Q1") (pin "2") (pinfunction "G_2") (pintype "passive"))
      (node (ref "U1") (pin "6") (pinfunction "PGATE_6") (pintype "bidirectional"))
    )
    (net (code "68") (name "Net-(Q1-S)") (class "Default")
      (node (ref "Q1") (pin "3") (pinfunction "S_3") (pintype "passive"))
      (node (ref "R_SNS") (pin "1") (pinfunction "1_1") (pintype "passive"))
      (node (ref "U1") (pin "7") (pinfunction "CSN_7") (pintype "bidirectional"))
    )
    (net (code "69") (name "Net-(RN1B-1)") (class "Default")
      (node (ref "RN1") (pin "2") (pinfunction "1_2") (pintype "passive"))
      (node (ref "U$4") (pin "P3") (pinfunction "D+_P3") (pintype "bidirectional"))
    )
    (net (code "70") (name "Net-(T1-D)") (class "Default")
      (node (ref "T1") (pin "1") (pinfunction "D_1") (pintype "passive"))
      (node (ref "U$4") (pin "P1") (pinfunction "VCC_P1") (pintype "bidirectional"))
    )
    (net (code "71") (name "Net-(T1-S)") (class "Default")
      (node (ref "C12") (pin "1") (pinfunction "1_1") (pintype "passive"))
      (node (ref "D1") (pin "C") (pinfunction "C_C") (pintype "passive"))
      (node (ref "T1") (pin "2") (pinfunction "S_2") (pintype "passive"))
      (node (ref "U3") (pin "VIN") (pinfunction "VIN_VIN") (pintype "input"))
    )
    (net (code "72") (name "Net-(U$4-D-)") (class "Default")
      (node (ref "RN1") (pin "1") (pinfunction "1_1") (pintype "passive"))
      (node (ref "U$4") (pin "P2") (pinfunction "D-_P2") (pintype "bidirectional"))
    )
    (net (code "73") (name "Net-(U1-COFF)") (class "Default")
      (node (ref "C_OFF") (pin "1") (pinfunction "1_1") (pintype "passive"))
      (node (ref "R_OFF") (pin "2") (pinfunction "2_2") (pintype "passive"))
      (node (ref "U1") (pin "4") (pinfunction "COFF_4") (pintype "bidirectional"))
    )
    (net (code "74") (name "Net-(U1-EN)") (class "Default")
      (node (ref "R_PD") (pin "2") (pinfunction "2_2") (pintype "passive"))
      (node (ref "U1") (pin "3") (pinfunction "EN_3") (pintype "bidirectional"))
    )
    (net (code "75") (name "Net-(U1-UVLO)") (class "Default")
      (node (ref "R_UV1") (pin "2") (pinfunction "2_2") (pintype "passive"))
      (node (ref "R_UV2") (pin "1") (pinfunction "1_1") (pintype "passive"))
      (node (ref "U1") (pin "1") (pinfunction "UVLO_1") (pintype "bidirectional"))
    )
    (net (code "76") (name "Net-(U1-VCC)") (class "Default")
      (node (ref "C_F") (pin "2") (pinfunction "2_2") (pintype "passive"))
      (node (ref "U1") (pin "9") (pinfunction "VCC_9") (pintype "bidirectional"))
    )
    (net (code "77") (name "Net-(U2-RS)") (class "Default")
      (node (ref "R14") (pin "1") (pinfunction "1_1") (pintype "passive"))
      (node (ref "U2") (pin "8") (pinfunction "RS_8") (pintype "bidirectional"))
    )
    (net (code "78") (name "unconnected-(U$2-PadB1)") (class "Default")
      (node (ref "U$2") (pin "B1") (pinfunction "B1_B1") (pintype "bidirectional"))
    )
    (net (code "79") (name "unconnected-(U$2-PadB2)") (class "Default")
      (node (ref "U$2") (pin "B2") (pinfunction "B2_B2") (pintype "bidirectional"))
    )
    (net (code "80") (name "unconnected-(U$2-PadB3)") (class "Default")
      (node (ref "U$2") (pin "B3") (pinfunction "B3_B3") (pintype "bidirectional"))
    )
    (net (code "81") (name "unconnected-(U$2-PadB4)") (class "Default")
      (node (ref "U$2") (pin "B4") (pinfunction "B4_B4") (pintype "bidirectional"))
    )
    (net (code "82") (name "unconnected-(U$2-PadB11)") (class "Default")
      (node (ref "U$2") (pin "B11") (pinfunction "B11_B11") (pintype "bidirectional"))
    )
    (net (code "83") (name "unconnected-(U$2-PadB12)") (class "Default")
      (node (ref "U$2") (pin "B12") (pinfunction "B12_B12") (pintype "bidirectional"))
    )
    (net (code "84") (name "unconnected-(U$2-PadB13)") (class "Default")
      (node (ref "U$2") (pin "B13") (pinfunction "B13_B13") (pintype "bidirectional"))
    )
    (net (code "85") (name "unconnected-(U$2-PadB14)") (class "Default")
      (node (ref "U$2") (pin "B14") (pinfunction "B14_B14") (pintype "bidirectional"))
    )
    (net (code "86") (name "unconnected-(U$2-PadB15)") (class "Default")
      (node (ref "U$2") (pin "B15") (pinfunction "B15_B15") (pintype "bidirectional"))
    )
    (net (code "87") (name "unconnected-(U$2-PadB16)") (class "Default")
      (node (ref "U$2") (pin "B16") (pinfunction "B16_B16") (pintype "bidirectional"))
    )
    (net (code "88") (name "unconnected-(U$2-PadB17)") (class "Default")
      (node (ref "U$2") (pin "B17") (pinfunction "B17_B17") (pintype "bidirectional"))
    )
    (net (code "89") (name "unconnected-(U$2-PadB18)") (class "Default")
      (node (ref "U$2") (pin "B18") (pinfunction "B18_B18") (pintype "bidirectional"))
    )
    (net (code "90") (name "unconnected-(U$2-PadB19)") (class "Default")
      (node (ref "U$2") (pin "B19") (pinfunction "B19_B19") (pintype "bidirectional"))
    )
    (net (code "91") (name "unconnected-(U$2-PadB20)") (class "Default")
      (node (ref "U$2") (pin "B20") (pinfunction "B20_B20") (pintype "bidirectional"))
    )
    (net (code "92") (name "unconnected-(U$2-PadB21)") (class "Default")
      (node (ref "U$2") (pin "B21") (pinfunction "B21_B21") (pintype "bidirectional"))
    )
    (net (code "93") (name "unconnected-(U$2-PadB22)") (class "Default")
      (node (ref "U$2") (pin "B22") (pinfunction "B22_B22") (pintype "bidirectional"))
    )
    (net (code "94") (name "unconnected-(U$2-PadB23)") (class "Default")
      (node (ref "U$2") (pin "B23") (pinfunction "B23_B23") (pintype "bidirectional"))
    )
    (net (code "95") (name "unconnected-(U$2-PadB24)") (class "Default")
      (node (ref "U$2") (pin "B24") (pinfunction "B24_B24") (pintype "bidirectional"))
    )
    (net (code "96") (name "unconnected-(U$2-PadB25)") (class "Default")
      (node (ref "U$2") (pin "B25") (pinfunction "B25_B25") (pintype "bidirectional"))
    )
    (net (code "97") (name "unconnected-(U$2-PadB26)") (class "Default")
      (node (ref "U$2") (pin "B26") (pinfunction "B26_B26") (pintype "bidirectional"))
    )
    (net (code "98") (name "unconnected-(U$2-PadB27)") (class "Default")
      (node (ref "U$2") (pin "B27") (pinfunction "B27_B27") (pintype "bidirectional"))
    )
    (net (code "99") (name "unconnected-(U$2-PadB28)") (class "Default")
      (node (ref "U$2") (pin "B28") (pinfunction "B28_B28") (pintype "bidirectional"))
    )
    (net (code "100") (name "unconnected-(U$2-PadB31)") (class "Default")
      (node (ref "U$2") (pin "B31") (pinfunction "B31_B31") (pintype "bidirectional"))
    )
    (net (code "101") (name "unconnected-(U$2-PadB32)") (class "Default")
      (node (ref "U$2") (pin "B32") (pinfunction "B32_B32") (pintype "bidirectional"))
    )
    (net (code "102") (name "unconnected-(U$2-PadB34)") (class "Default")
      (node (ref "U$2") (pin "B34") (pinfunction "B34_B34") (pintype "bidirectional"))
    )
    (net (code "103") (name "unconnected-(U$2-PadB36)") (class "Default")
      (node (ref "U$2") (pin "B36") (pinfunction "B36_B36") (pintype "bidirectional"))
    )
    (net (code "104") (name "unconnected-(U$2-PadB37)") (class "Default")
      (node (ref "U$2") (pin "B37") (pinfunction "B37_B37") (pintype "bidirectional"))
    )
    (net (code "105") (name "unconnected-(U$2-PadB38)") (class "Default")
      (node (ref "U$2") (pin "B38") (pinfunction "B38_B38") (pintype "bidirectional"))
    )
    (net (code "106") (name "unconnected-(U$2-PadB39)") (class "Default")
      (node (ref "U$2") (pin "B39") (pinfunction "B39_B39") (pintype "bidirectional"))
    )
    (net (code "107") (name "unconnected-(U$2-PadB40)") (class "Default")
      (node (ref "U$2") (pin "B40") (pinfunction "B40_B40") (pintype "bidirectional"))
    )
    (net (code "108") (name "unconnected-(U$2-PadT5)") (class "Default")
      (node (ref "U$2") (pin "T5") (pinfunction "T5_T5") (pintype "bidirectional"))
    )
    (net (code "109") (name "unconnected-(U$2-PadT6)") (class "Default")
      (node (ref "U$2") (pin "T6") (pinfunction "T6_T6") (pintype "bidirectional"))
    )
    (net (code "110") (name "unconnected-(U$2-PadT7)") (class "Default")
      (node (ref "U$2") (pin "T7") (pinfunction "T7_T7") (pintype "bidirectional"))
    )
    (net (code "111") (name "unconnected-(U$2-PadT8)") (class "Default")
      (node (ref "U$2") (pin "T8") (pinfunction "T8_T8") (pintype "bidirectional"))
    )
    (net (code "112") (name "unconnected-(U$2-PadT9)") (class "Default")
      (node (ref "U$2") (pin "T9") (pinfunction "T9_T9") (pintype "bidirectional"))
    )
    (net (code "113") (name "unconnected-(U$2-PadT10)") (class "Default")
      (node (ref "U$2") (pin "T10") (pinfunction "T10_T10") (pintype "bidirectional"))
    )
    (net (code "114") (name "unconnected-(U$2-PadT18)") (class "Default")
      (node (ref "U$2") (pin "T18") (pinfunction "T18_T18") (pintype "bidirectional"))
    )
    (net (code "115") (name "unconnected-(U$2-PadT27)") (class "Default")
      (node (ref "U$2") (pin "T27") (pinfunction "T27_T27") (pintype "bidirectional"))
    )
    (net (code "116") (name "unconnected-(U$2-PadT28)") (class "Default")
      (node (ref "U$2") (pin "T28") (pinfunction "T28_T28") (pintype "bidirectional"))
    )
    (net (code "117") (name "unconnected-(U$2-PadT29)") (class "Default")
      (node (ref "U$2") (pin "T29") (pinfunction "T29_T29") (pintype "bidirectional"))
    )
    (net (code "118") (name "unconnected-(U$2-PadT30)") (class "Default")
      (node (ref "U$2") (pin "T30") (pinfunction "T30_T30") (pintype "bidirectional"))
    )
    (net (code "119") (name "unconnected-(U$2-PadT31)") (class "Default")
      (node (ref "U$2") (pin "T31") (pinfunction "T31_T31") (pintype "bidirectional"))
    )
    (net (code "120") (name "unconnected-(U$2-PadT32)") (class "Default")
      (node (ref "U$2") (pin "T32") (pinfunction "T32_T32") (pintype "bidirectional"))
    )
    (net (code "121") (name "unconnected-(U$2-PadT33)") (class "Default")
      (node (ref "U$2") (pin "T33") (pinfunction "T33_T33") (pintype "bidirectional"))
    )
    (net (code "122") (name "unconnected-(U$2-PadT34)") (class "Default")
      (node (ref "U$2") (pin "T34") (pinfunction "T34_T34") (pintype "bidirectional"))
    )
    (net (code "123") (name "unconnected-(U$2-PadT35)") (class "Default")
      (node (ref "U$2") (pin "T35") (pinfunction "T35_T35") (pintype "bidirectional"))
    )
    (net (code "124") (name "unconnected-(U$2-PadT36)") (class "Default")
      (node (ref "U$2") (pin "T36") (pinfunction "T36_T36") (pintype "bidirectional"))
    )
    (net (code "125") (name "unconnected-(U$2-PadT37)") (class "Default")
      (node (ref "U$2") (pin "T37") (pinfunction "T37_T37") (pintype "bidirectional"))
    )
    (net (code "126") (name "unconnected-(U$2-PadT38)") (class "Default")
      (node (ref "U$2") (pin "T38") (pinfunction "T38_T38") (pintype "bidirectional"))
    )
    (net (code "127") (name "unconnected-(U$2-PadT39)") (class "Default")
      (node (ref "U$2") (pin "T39") (pinfunction "T39_T39") (pintype "bidirectional"))
    )
    (net (code "128") (name "unconnected-(U$2-PadT40)") (class "Default")
      (node (ref "U$2") (pin "T40") (pinfunction "T40_T40") (pintype "bidirectional"))
    )
    (net (code "129") (name "unconnected-(U1-IADJ-Pad2)") (class "Default")
      (node (ref "U1") (pin "2") (pinfunction "IADJ_2") (pintype "bidirectional"))
    )
    (net (code "130") (name "unconnected-(U2-SHDN-Pad5)") (class "Default")
      (node (ref "U2") (pin "5") (pinfunction "SHDN_5") (pintype "bidirectional"))
    )
    (net (code "131") (name "unconnected-(Y1-OE-Pad1)") (class "Default")
      (node (ref "Y1") (pin "1") (pinfunction "OE_1") (pintype "input"))
    )
  )
)
